# SCH_Argon_flow_controller_2021-09-10.net
KiCad netlist of a schematic drawn in EasyEDA
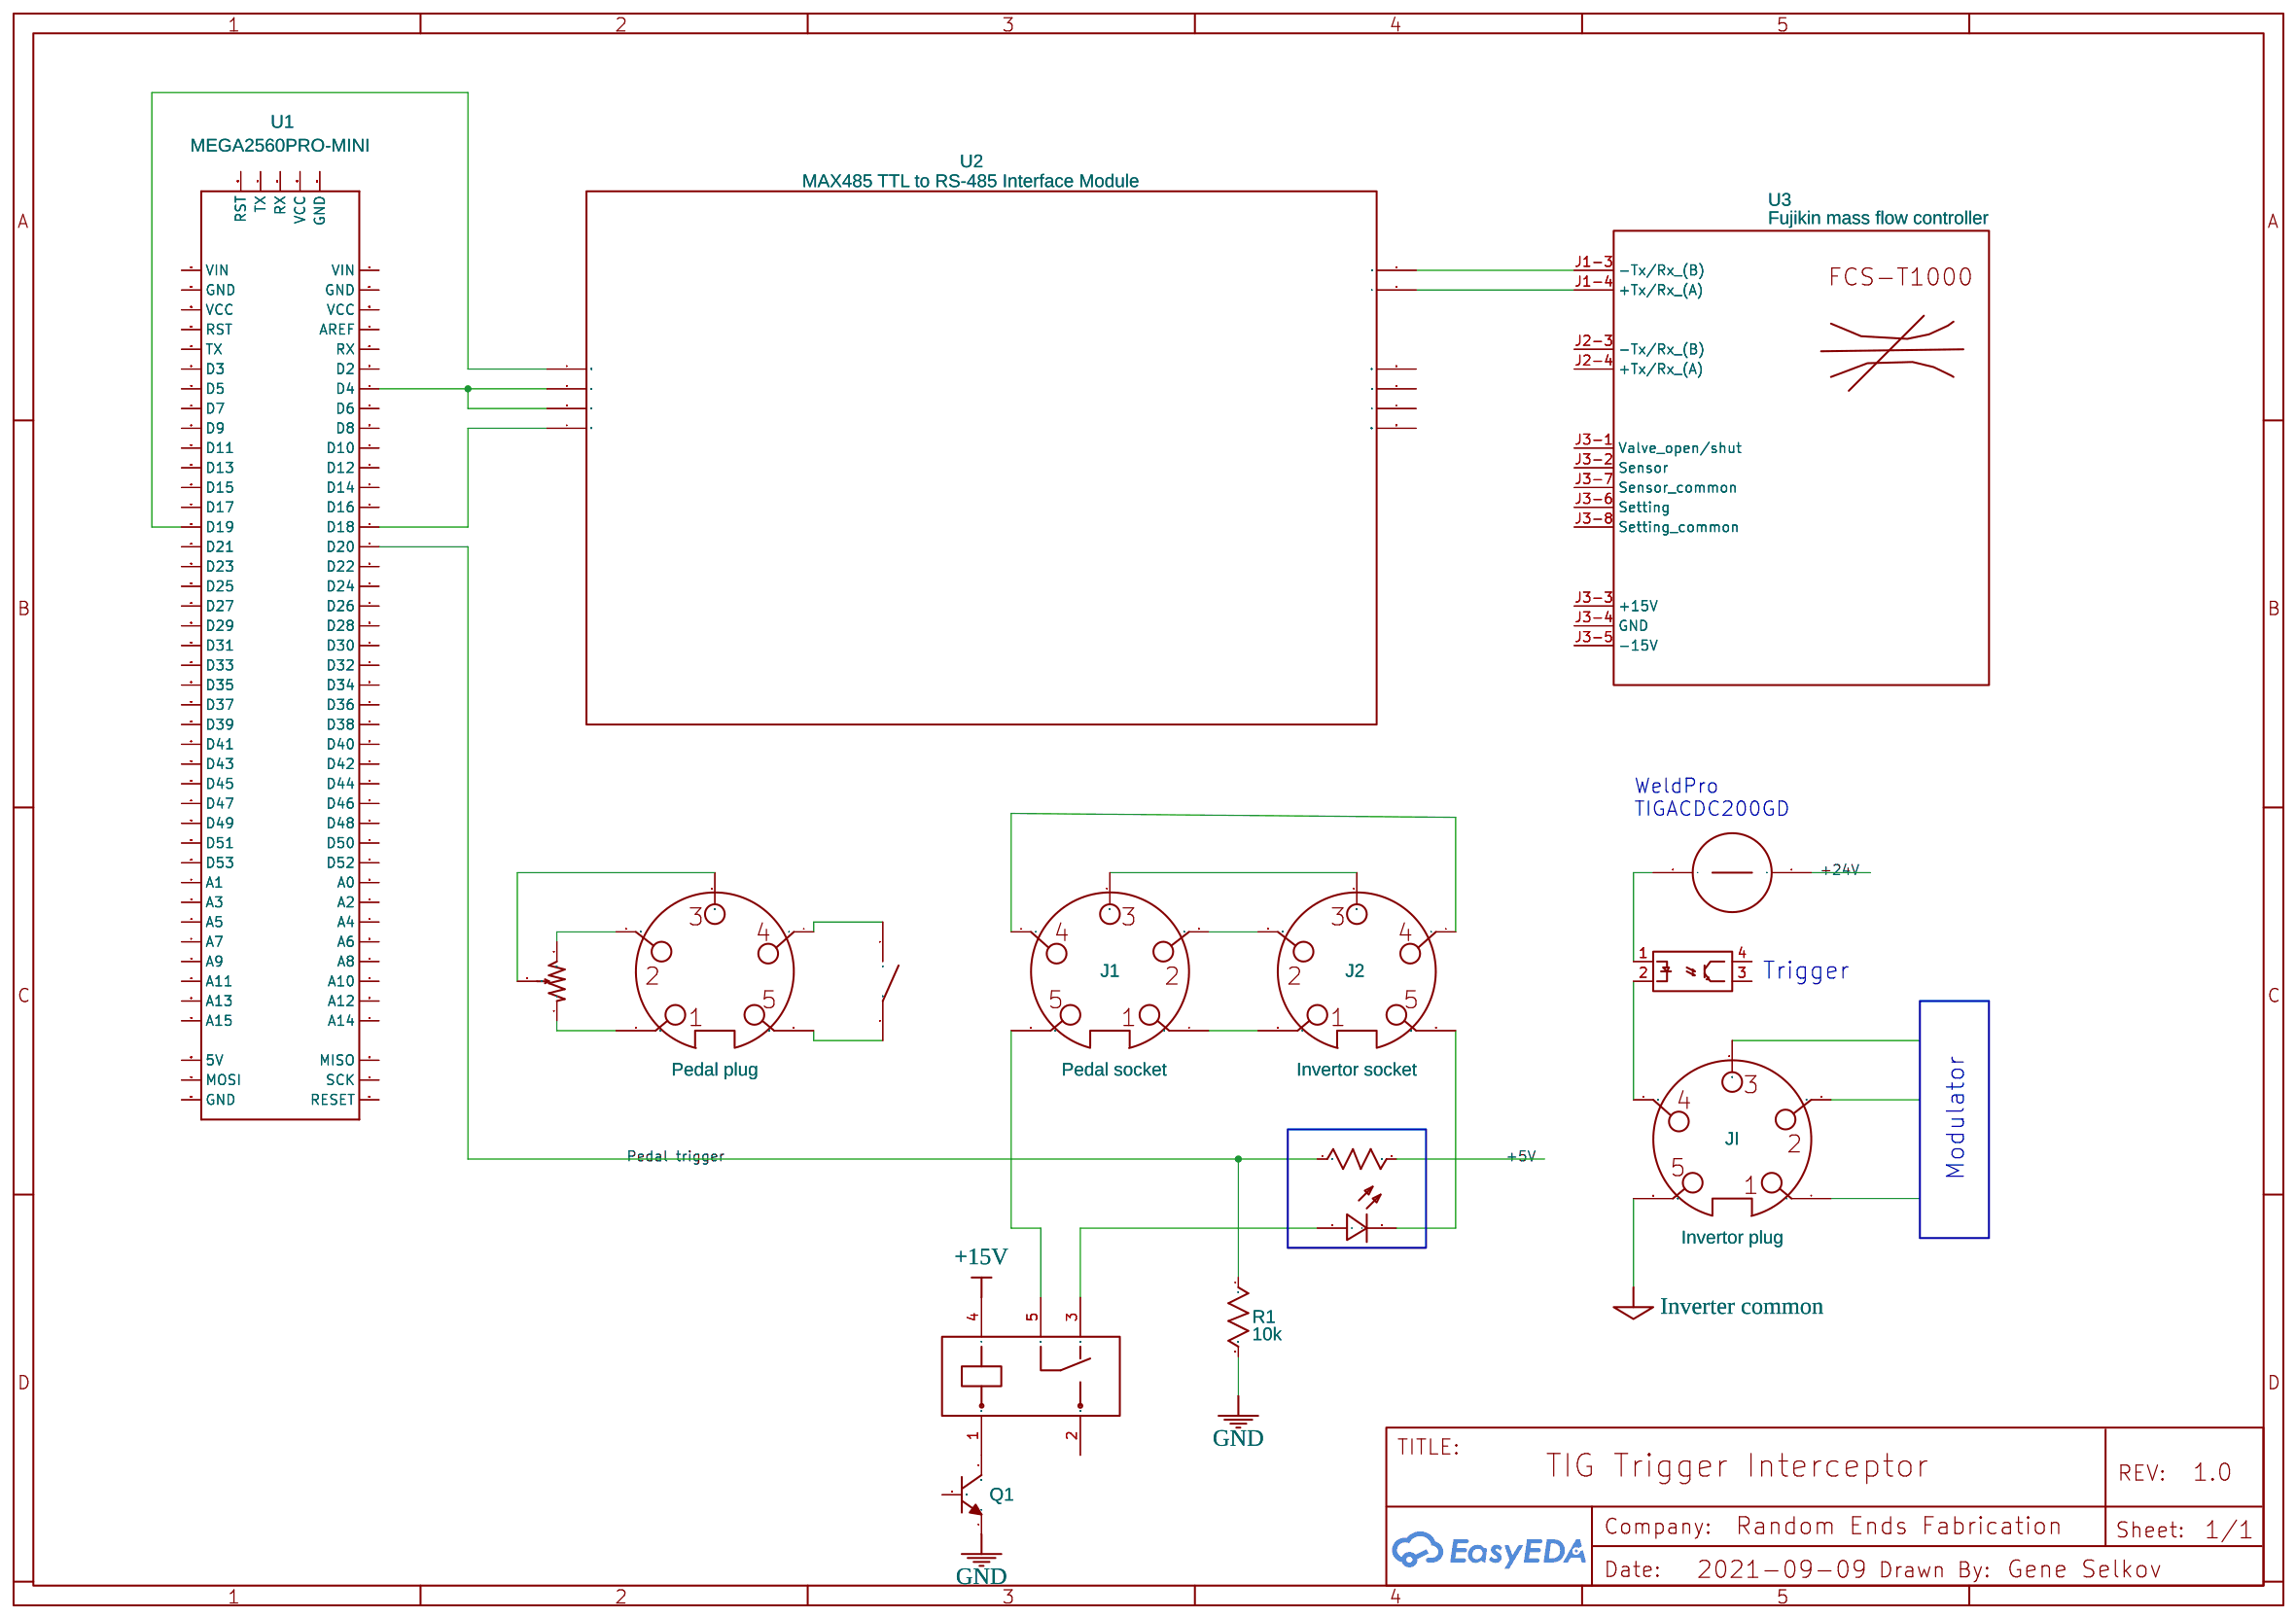
[diagram p0: schematic sheet]

(export (version "E")
  (design (tool "Eeschema 10.0.6"))
  (components
    (comp (ref "CS") (value "Current source") (libsource (lib "") (part "Current source")))
    (comp (ref "IC1")
      (value "Trigger")
      (libsource (lib "") (part "Optocoupler_SMD_KPC357_LTV35x_PC357_SingleChannel"))
    )
    (comp (ref "J0")
      (value "Pedal plug")
      (fields
        (field (name "BOM_Manufacturer Part") "Unknown")
        (field (name "BOM_Supplier Part") "CON-HK1705")
      )
      (libsource (lib "") (part "Weipu 5 connector"))
    )
    (comp (ref "J1")
      (value "Pedal socket")
      (fields
        (field (name "BOM_Manufacturer Part") "Unknown")
        (field (name "BOM_Supplier Part") "CON-HK1705")
      )
      (libsource (lib "") (part "Weipu 5 connector_3"))
    )
    (comp (ref "J2")
      (value "Invertor socket")
      (fields
        (field (name "BOM_Manufacturer Part") "Unknown")
        (field (name "BOM_Supplier Part") "CON-HK1705")
      )
      (libsource (lib "") (part "Weipu 5 connector_2"))
    )
    (comp (ref "JI")
      (value "Invertor plug")
      (fields
        (field (name "BOM_Manufacturer Part") "Unknown")
        (field (name "BOM_Supplier Part") "CON-HK1705")
      )
      (libsource (lib "") (part "Weipu 5 connector_1"))
    )
    (comp (ref "LED1")
      (value "LED-Red(0805)")
      (fields
        (field (name "BOM_Manufacturer Part") "17-21SURC/S530-A2/TR8")
        (field (name "BOM_Supplier Part") "C131244")
      )
      (libsource (lib "") (part "LED-Red(0805)"))
    )
    (comp (ref "PHR") (value "1 .. 40k") (libsource (lib "") (part "R_0603_US_1")))
    (comp (ref "POT") (value "POTENTIOMETER") (libsource (lib "") (part "POTENTIOMETER")))
    (comp (ref "Q1")
      (value "MPSA06-AT/P")
      (fields (field (name "BOM_Supplier Part") "C112894"))
      (libsource (lib "") (part "MPSA06-AT/P"))
    )
    (comp (ref "R1") (value "10k") (libsource (lib "") (part "R_0603_US")))
    (comp (ref "RELAY1")
      (value "SRD-12VDC-SL-C")
      (fields (field (name "BOM_Supplier Part") "C30431"))
      (libsource (lib "") (part "SRD-12VDC-SL-C"))
    )
    (comp (ref "S1") (value "Switch") (libsource (lib "") (part "Switch")))
    (comp (ref "U1") (value "MEGA2560PRO-MINI") (libsource (lib "") (part "MEGA2560PRO-MINI")))
    (comp (ref "U2")
      (value "MAX485 TTL to RS-485 Interface Module")
      (libsource (lib "") (part "MAX485 TTL to RS-485 Interface Module"))
    )
    (comp (ref "U3")
      (value "Fujikin mass flow controller")
      (fields (field (name "BOM_Manufacturer Part") "FCS-T1000"))
      (libsource (lib "") (part "Fujikin mass flow controller"))
    )
  )
  (nets
    (net (code "1") (name "+15V") (class "Default")
      (node (ref "RELAY1") (pin "4") (pinfunction "4_4") (pintype "input"))
    )
    (net (code "2") (name "/+5V") (class "Default")
      (node (ref "PHR") (pin "2") (pinfunction "2_2") (pintype "unspecified"))
    )
    (net (code "3") (name "/+24V") (class "Default")
      (node (ref "CS") (pin "1") (pinfunction "+_1") (pintype "unspecified"))
    )
    (net (code "4") (name "/Pedal trigger") (class "Default")
      (node (ref "PHR") (pin "1") (pinfunction "1_1") (pintype "unspecified"))
      (node (ref "R1") (pin "1") (pinfunction "1_1") (pintype "unspecified"))
      (node (ref "U1") (pin "D20") (pinfunction "D20_D20") (pintype "bidirectional"))
    )
    (net (code "5") (name "GND") (class "Default")
      (node (ref "Q1") (pin "1") (pinfunction "E_1") (pintype "input"))
      (node (ref "R1") (pin "2") (pinfunction "2_2") (pintype "unspecified"))
    )
    (net (code "6") (name "Inverter common") (class "Default")
      (node (ref "JI") (pin "5") (pinfunction "5_5") (pintype "unspecified"))
    )
    (net (code "7") (name "Net-(CS--)") (class "Default")
      (node (ref "CS") (pin "2") (pinfunction "-_2") (pintype "unspecified"))
      (node (ref "IC1") (pin "1") (pintype "unspecified"))
    )
    (net (code "8") (name "Net-(IC1-Pad2)") (class "Default")
      (node (ref "IC1") (pin "2") (pintype "unspecified"))
      (node (ref "JI") (pin "4") (pinfunction "4_4") (pintype "unspecified"))
    )
    (net (code "9") (name "Net-(J0-Pad1)") (class "Default")
      (node (ref "J0") (pin "1") (pinfunction "1_1") (pintype "unspecified"))
      (node (ref "POT") (pin "1") (pinfunction "1_1") (pintype "unspecified"))
    )
    (net (code "10") (name "Net-(J0-Pad2)") (class "Default")
      (node (ref "J0") (pin "2") (pinfunction "2_2") (pintype "unspecified"))
      (node (ref "POT") (pin "2") (pinfunction "2_2") (pintype "unspecified"))
    )
    (net (code "11") (name "Net-(J0-Pad3)") (class "Default")
      (node (ref "J0") (pin "3") (pinfunction "3_3") (pintype "unspecified"))
      (node (ref "POT") (pin "3") (pinfunction "3_3") (pintype "unspecified"))
    )
    (net (code "12") (name "Net-(J0-Pad4)") (class "Default")
      (node (ref "J0") (pin "4") (pinfunction "4_4") (pintype "unspecified"))
      (node (ref "S1") (pin "1") (pinfunction "1_1") (pintype "unspecified"))
    )
    (net (code "13") (name "Net-(J0-Pad5)") (class "Default")
      (node (ref "J0") (pin "5") (pinfunction "5_5") (pintype "unspecified"))
      (node (ref "S1") (pin "2") (pinfunction "2_2") (pintype "unspecified"))
    )
    (net (code "14") (name "Net-(J1-Pad1)") (class "Default")
      (node (ref "J1") (pin "1") (pinfunction "1_1") (pintype "unspecified"))
      (node (ref "J2") (pin "1") (pinfunction "1_1") (pintype "unspecified"))
    )
    (net (code "15") (name "Net-(J1-Pad2)") (class "Default")
      (node (ref "J1") (pin "2") (pinfunction "2_2") (pintype "unspecified"))
      (node (ref "J2") (pin "2") (pinfunction "2_2") (pintype "unspecified"))
    )
    (net (code "16") (name "Net-(J1-Pad3)") (class "Default")
      (node (ref "J1") (pin "3") (pinfunction "3_3") (pintype "unspecified"))
      (node (ref "J2") (pin "3") (pinfunction "3_3") (pintype "unspecified"))
    )
    (net (code "17") (name "Net-(J1-Pad4)") (class "Default")
      (node (ref "J1") (pin "4") (pinfunction "4_4") (pintype "unspecified"))
      (node (ref "J2") (pin "4") (pinfunction "4_4") (pintype "unspecified"))
    )
    (net (code "18") (name "Net-(J1-Pad5)") (class "Default")
      (node (ref "J1") (pin "5") (pinfunction "5_5") (pintype "unspecified"))
      (node (ref "RELAY1") (pin "5") (pinfunction "5_5") (pintype "input"))
    )
    (net (code "19") (name "Net-(LED1-+)") (class "Default")
      (node (ref "LED1") (pin "1") (pinfunction "+_1") (pintype "unspecified"))
      (node (ref "RELAY1") (pin "3") (pinfunction "3_3") (pintype "input"))
    )
    (net (code "20") (name "Net-(LED1--)") (class "Default")
      (node (ref "J2") (pin "5") (pinfunction "5_5") (pintype "unspecified"))
      (node (ref "LED1") (pin "2") (pinfunction "-_2") (pintype "unspecified"))
    )
    (net (code "21") (name "Net-(Q1-C)") (class "Default")
      (node (ref "Q1") (pin "3") (pinfunction "C_3") (pintype "input"))
      (node (ref "RELAY1") (pin "1") (pinfunction "1_1") (pintype "input"))
    )
    (net (code "22") (name "Net-(U2-A-Pad10)") (class "Default")
      (node (ref "U2") (pin "10") (pinfunction "A_10") (pintype "bidirectional"))
      (node (ref "U3") (pin "J1-4") (pinfunction "+Tx/Rx_(A)_J1-4") (pintype "bidirectional"))
    )
    (net (code "23") (name "Net-(U2-B-Pad9)") (class "Default")
      (node (ref "U2") (pin "9") (pinfunction "B_9") (pintype "bidirectional"))
      (node (ref "U3") (pin "J1-3") (pinfunction "-Tx/Rx_(B)_J1-3") (pintype "bidirectional"))
    )
    (net (code "24") (name "Net-(U2-DE)") (class "Default")
      (node (ref "U1") (pin "D4") (pinfunction "D4_D4") (pintype "bidirectional"))
      (node (ref "U2") (pin "2") (pinfunction "RE_2") (pintype "input"))
      (node (ref "U2") (pin "3") (pinfunction "DE_3") (pintype "input"))
    )
    (net (code "25") (name "Net-(U2-DI)") (class "Default")
      (node (ref "U1") (pin "D18") (pinfunction "D18_D18") (pintype "bidirectional"))
      (node (ref "U2") (pin "4") (pinfunction "DI_4") (pintype "input"))
    )
    (net (code "26") (name "Net-(U2-RO)") (class "Default")
      (node (ref "U1") (pin "D19") (pinfunction "D19_D19") (pintype "bidirectional"))
      (node (ref "U2") (pin "1") (pinfunction "RO_1") (pintype "output"))
    )
    (net (code "27") (name "unconnected-(IC1-Pad3)") (class "Default")
      (node (ref "IC1") (pin "3") (pintype "unspecified"))
    )
    (net (code "28") (name "unconnected-(IC1-Pad4)") (class "Default")
      (node (ref "IC1") (pin "4") (pintype "unspecified"))
    )
    (net (code "29") (name "unconnected-(JI-Pad1)") (class "Default")
      (node (ref "JI") (pin "1") (pinfunction "1_1") (pintype "unspecified"))
    )
    (net (code "30") (name "unconnected-(JI-Pad2)") (class "Default")
      (node (ref "JI") (pin "2") (pinfunction "2_2") (pintype "unspecified"))
    )
    (net (code "31") (name "unconnected-(JI-Pad3)") (class "Default")
      (node (ref "JI") (pin "3") (pinfunction "3_3") (pintype "unspecified"))
    )
    (net (code "32") (name "unconnected-(Q1-B-Pad2)") (class "Default")
      (node (ref "Q1") (pin "2") (pinfunction "B_2") (pintype "input"))
    )
    (net (code "33") (name "unconnected-(RELAY1-Pad2)") (class "Default")
      (node (ref "RELAY1") (pin "2") (pinfunction "2_2") (pintype "input"))
    )
    (net (code "34") (name "unconnected-(U1-5V-Pad5V@3)") (class "Default")
      (node (ref "U1") (pin "5V@3") (pinfunction "5V_5V@3") (pintype "bidirectional"))
    )
    (net (code "35") (name "unconnected-(U1-GND-PadGND@1)") (class "Default")
      (node (ref "U1") (pin "GND@1") (pinfunction "GND_GND@1") (pintype "bidirectional"))
    )
    (net (code "36") (name "unconnected-(U1-GND-PadGND@2)") (class "Default")
      (node (ref "U1") (pin "GND@2") (pinfunction "GND_GND@2") (pintype "bidirectional"))
    )
    (net (code "37") (name "unconnected-(U1-GND-PadGND@3)") (class "Default")
      (node (ref "U1") (pin "GND@3") (pinfunction "GND_GND@3") (pintype "bidirectional"))
    )
    (net (code "38") (name "unconnected-(U1-GND-PadGND@4)") (class "Default")
      (node (ref "U1") (pin "GND@4") (pinfunction "GND_GND@4") (pintype "bidirectional"))
    )
    (net (code "39") (name "unconnected-(U1-PadA0)") (class "Default")
      (node (ref "U1") (pin "A0") (pinfunction "A0_A0") (pintype "bidirectional"))
    )
    (net (code "40") (name "unconnected-(U1-PadA1)") (class "Default")
      (node (ref "U1") (pin "A1") (pinfunction "A1_A1") (pintype "bidirectional"))
    )
    (net (code "41") (name "unconnected-(U1-PadA2)") (class "Default")
      (node (ref "U1") (pin "A2") (pinfunction "A2_A2") (pintype "bidirectional"))
    )
    (net (code "42") (name "unconnected-(U1-PadA3)") (class "Default")
      (node (ref "U1") (pin "A3") (pinfunction "A3_A3") (pintype "bidirectional"))
    )
    (net (code "43") (name "unconnected-(U1-PadA4)") (class "Default")
      (node (ref "U1") (pin "A4") (pinfunction "A4_A4") (pintype "bidirectional"))
    )
    (net (code "44") (name "unconnected-(U1-PadA5)") (class "Default")
      (node (ref "U1") (pin "A5") (pinfunction "A5_A5") (pintype "bidirectional"))
    )
    (net (code "45") (name "unconnected-(U1-PadA6)") (class "Default")
      (node (ref "U1") (pin "A6") (pinfunction "A6_A6") (pintype "bidirectional"))
    )
    (net (code "46") (name "unconnected-(U1-PadA7)") (class "Default")
      (node (ref "U1") (pin "A7") (pinfunction "A7_A7") (pintype "bidirectional"))
    )
    (net (code "47") (name "unconnected-(U1-PadA8)") (class "Default")
      (node (ref "U1") (pin "A8") (pinfunction "A8_A8") (pintype "bidirectional"))
    )
    (net (code "48") (name "unconnected-(U1-PadA9)") (class "Default")
      (node (ref "U1") (pin "A9") (pinfunction "A9_A9") (pintype "bidirectional"))
    )
    (net (code "49") (name "unconnected-(U1-PadA10)") (class "Default")
      (node (ref "U1") (pin "A10") (pinfunction "A10_A10") (pintype "bidirectional"))
    )
    (net (code "50") (name "unconnected-(U1-PadA11)") (class "Default")
      (node (ref "U1") (pin "A11") (pinfunction "A11_A11") (pintype "bidirectional"))
    )
    (net (code "51") (name "unconnected-(U1-PadA12)") (class "Default")
      (node (ref "U1") (pin "A12") (pinfunction "A12_A12") (pintype "bidirectional"))
    )
    (net (code "52") (name "unconnected-(U1-PadA13)") (class "Default")
      (node (ref "U1") (pin "A13") (pinfunction "A13_A13") (pintype "bidirectional"))
    )
    (net (code "53") (name "unconnected-(U1-PadA14)") (class "Default")
      (node (ref "U1") (pin "A14") (pinfunction "A14_A14") (pintype "bidirectional"))
    )
    (net (code "54") (name "unconnected-(U1-PadA15)") (class "Default")
      (node (ref "U1") (pin "A15") (pinfunction "A15_A15") (pintype "bidirectional"))
    )
    (net (code "55") (name "unconnected-(U1-PadAREF)") (class "Default")
      (node (ref "U1") (pin "AREF") (pinfunction "AREF_AREF") (pintype "bidirectional"))
    )
    (net (code "56") (name "unconnected-(U1-PadD2)") (class "Default")
      (node (ref "U1") (pin "D2") (pinfunction "D2_D2") (pintype "bidirectional"))
    )
    (net (code "57") (name "unconnected-(U1-PadD3)") (class "Default")
      (node (ref "U1") (pin "D3") (pinfunction "D3_D3") (pintype "bidirectional"))
    )
    (net (code "58") (name "unconnected-(U1-PadD5)") (class "Default")
      (node (ref "U1") (pin "D5") (pinfunction "D5_D5") (pintype "bidirectional"))
    )
    (net (code "59") (name "unconnected-(U1-PadD6)") (class "Default")
      (node (ref "U1") (pin "D6") (pinfunction "D6_D6") (pintype "bidirectional"))
    )
    (net (code "60") (name "unconnected-(U1-PadD7)") (class "Default")
      (node (ref "U1") (pin "D7") (pinfunction "D7_D7") (pintype "bidirectional"))
    )
    (net (code "61") (name "unconnected-(U1-PadD8)") (class "Default")
      (node (ref "U1") (pin "D8") (pinfunction "D8_D8") (pintype "bidirectional"))
    )
    (net (code "62") (name "unconnected-(U1-PadD9)") (class "Default")
      (node (ref "U1") (pin "D9") (pinfunction "D9_D9") (pintype "bidirectional"))
    )
    (net (code "63") (name "unconnected-(U1-PadD10)") (class "Default")
      (node (ref "U1") (pin "D10") (pinfunction "D10_D10") (pintype "bidirectional"))
    )
    (net (code "64") (name "unconnected-(U1-PadD11)") (class "Default")
      (node (ref "U1") (pin "D11") (pinfunction "D11_D11") (pintype "bidirectional"))
    )
    (net (code "65") (name "unconnected-(U1-PadD12)") (class "Default")
      (node (ref "U1") (pin "D12") (pinfunction "D12_D12") (pintype "bidirectional"))
    )
    (net (code "66") (name "unconnected-(U1-PadD13)") (class "Default")
      (node (ref "U1") (pin "D13") (pinfunction "D13_D13") (pintype "bidirectional"))
    )
    (net (code "67") (name "unconnected-(U1-PadD14)") (class "Default")
      (node (ref "U1") (pin "D14") (pinfunction "D14_D14") (pintype "bidirectional"))
    )
    (net (code "68") (name "unconnected-(U1-PadD15)") (class "Default")
      (node (ref "U1") (pin "D15") (pinfunction "D15_D15") (pintype "bidirectional"))
    )
    (net (code "69") (name "unconnected-(U1-PadD16)") (class "Default")
      (node (ref "U1") (pin "D16") (pinfunction "D16_D16") (pintype "bidirectional"))
    )
    (net (code "70") (name "unconnected-(U1-PadD17)") (class "Default")
      (node (ref "U1") (pin "D17") (pinfunction "D17_D17") (pintype "bidirectional"))
    )
    (net (code "71") (name "unconnected-(U1-PadD21)") (class "Default")
      (node (ref "U1") (pin "D21") (pinfunction "D21_D21") (pintype "bidirectional"))
    )
    (net (code "72") (name "unconnected-(U1-PadD22)") (class "Default")
      (node (ref "U1") (pin "D22") (pinfunction "D22_D22") (pintype "bidirectional"))
    )
    (net (code "73") (name "unconnected-(U1-PadD23)") (class "Default")
      (node (ref "U1") (pin "D23") (pinfunction "D23_D23") (pintype "bidirectional"))
    )
    (net (code "74") (name "unconnected-(U1-PadD24)") (class "Default")
      (node (ref "U1") (pin "D24") (pinfunction "D24_D24") (pintype "bidirectional"))
    )
    (net (code "75") (name "unconnected-(U1-PadD25)") (class "Default")
      (node (ref "U1") (pin "D25") (pinfunction "D25_D25") (pintype "bidirectional"))
    )
    (net (code "76") (name "unconnected-(U1-PadD26)") (class "Default")
      (node (ref "U1") (pin "D26") (pinfunction "D26_D26") (pintype "bidirectional"))
    )
    (net (code "77") (name "unconnected-(U1-PadD27)") (class "Default")
      (node (ref "U1") (pin "D27") (pinfunction "D27_D27") (pintype "bidirectional"))
    )
    (net (code "78") (name "unconnected-(U1-PadD28)") (class "Default")
      (node (ref "U1") (pin "D28") (pinfunction "D28_D28") (pintype "bidirectional"))
    )
    (net (code "79") (name "unconnected-(U1-PadD29)") (class "Default")
      (node (ref "U1") (pin "D29") (pinfunction "D29_D29") (pintype "bidirectional"))
    )
    (net (code "80") (name "unconnected-(U1-PadD30)") (class "Default")
      (node (ref "U1") (pin "D30") (pinfunction "D30_D30") (pintype "bidirectional"))
    )
    (net (code "81") (name "unconnected-(U1-PadD31)") (class "Default")
      (node (ref "U1") (pin "D31") (pinfunction "D31_D31") (pintype "bidirectional"))
    )
    (net (code "82") (name "unconnected-(U1-PadD32)") (class "Default")
      (node (ref "U1") (pin "D32") (pinfunction "D32_D32") (pintype "bidirectional"))
    )
    (net (code "83") (name "unconnected-(U1-PadD33)") (class "Default")
      (node (ref "U1") (pin "D33") (pinfunction "D33_D33") (pintype "bidirectional"))
    )
    (net (code "84") (name "unconnected-(U1-PadD34)") (class "Default")
      (node (ref "U1") (pin "D34") (pinfunction "D34_D34") (pintype "bidirectional"))
    )
    (net (code "85") (name "unconnected-(U1-PadD35)") (class "Default")
      (node (ref "U1") (pin "D35") (pinfunction "D35_D35") (pintype "bidirectional"))
    )
    (net (code "86") (name "unconnected-(U1-PadD36)") (class "Default")
      (node (ref "U1") (pin "D36") (pinfunction "D36_D36") (pintype "bidirectional"))
    )
    (net (code "87") (name "unconnected-(U1-PadD37)") (class "Default")
      (node (ref "U1") (pin "D37") (pinfunction "D37_D37") (pintype "bidirectional"))
    )
    (net (code "88") (name "unconnected-(U1-PadD38)") (class "Default")
      (node (ref "U1") (pin "D38") (pinfunction "D38_D38") (pintype "bidirectional"))
    )
    (net (code "89") (name "unconnected-(U1-PadD39)") (class "Default")
      (node (ref "U1") (pin "D39") (pinfunction "D39_D39") (pintype "bidirectional"))
    )
    (net (code "90") (name "unconnected-(U1-PadD40)") (class "Default")
      (node (ref "U1") (pin "D40") (pinfunction "D40_D40") (pintype "bidirectional"))
    )
    (net (code "91") (name "unconnected-(U1-PadD41)") (class "Default")
      (node (ref "U1") (pin "D41") (pinfunction "D41_D41") (pintype "bidirectional"))
    )
    (net (code "92") (name "unconnected-(U1-PadD42)") (class "Default")
      (node (ref "U1") (pin "D42") (pinfunction "D42_D42") (pintype "bidirectional"))
    )
    (net (code "93") (name "unconnected-(U1-PadD43)") (class "Default")
      (node (ref "U1") (pin "D43") (pinfunction "D43_D43") (pintype "bidirectional"))
    )
    (net (code "94") (name "unconnected-(U1-PadD44)") (class "Default")
      (node (ref "U1") (pin "D44") (pinfunction "D44_D44") (pintype "bidirectional"))
    )
    (net (code "95") (name "unconnected-(U1-PadD45)") (class "Default")
      (node (ref "U1") (pin "D45") (pinfunction "D45_D45") (pintype "bidirectional"))
    )
    (net (code "96") (name "unconnected-(U1-PadD46)") (class "Default")
      (node (ref "U1") (pin "D46") (pinfunction "D46_D46") (pintype "bidirectional"))
    )
    (net (code "97") (name "unconnected-(U1-PadD47)") (class "Default")
      (node (ref "U1") (pin "D47") (pinfunction "D47_D47") (pintype "bidirectional"))
    )
    (net (code "98") (name "unconnected-(U1-PadD48)") (class "Default")
      (node (ref "U1") (pin "D48") (pinfunction "D48_D48") (pintype "bidirectional"))
    )
    (net (code "99") (name "unconnected-(U1-PadD49)") (class "Default")
      (node (ref "U1") (pin "D49") (pinfunction "D49_D49") (pintype "bidirectional"))
    )
    (net (code "100") (name "unconnected-(U1-PadD50)") (class "Default")
      (node (ref "U1") (pin "D50") (pinfunction "D50_D50") (pintype "bidirectional"))
    )
    (net (code "101") (name "unconnected-(U1-PadD51)") (class "Default")
      (node (ref "U1") (pin "D51") (pinfunction "D51_D51") (pintype "bidirectional"))
    )
    (net (code "102") (name "unconnected-(U1-PadD52)") (class "Default")
      (node (ref "U1") (pin "D52") (pinfunction "D52_D52") (pintype "bidirectional"))
    )
    (net (code "103") (name "unconnected-(U1-PadD53)") (class "Default")
      (node (ref "U1") (pin "D53") (pinfunction "D53_D53") (pintype "bidirectional"))
    )
    (net (code "104") (name "unconnected-(U1-PadMISO)") (class "Default")
      (node (ref "U1") (pin "MISO") (pinfunction "MISO_MISO") (pintype "bidirectional"))
    )
    (net (code "105") (name "unconnected-(U1-PadMOSI)") (class "Default")
      (node (ref "U1") (pin "MOSI") (pinfunction "MOSI_MOSI") (pintype "bidirectional"))
    )
    (net (code "106") (name "unconnected-(U1-PadRESET)") (class "Default")
      (node (ref "U1") (pin "RESET") (pinfunction "RESET_RESET") (pintype "bidirectional"))
    )
    (net (code "107") (name "unconnected-(U1-PadSCK)") (class "Default")
      (node (ref "U1") (pin "SCK") (pinfunction "SCK_SCK") (pintype "bidirectional"))
    )
    (net (code "108") (name "unconnected-(U1-RST-PadRST@1)") (class "Default")
      (node (ref "U1") (pin "RST@1") (pinfunction "RST_RST@1") (pintype "bidirectional"))
    )
    (net (code "109") (name "unconnected-(U1-RST-PadRST@2)") (class "Default")
      (node (ref "U1") (pin "RST@2") (pinfunction "RST_RST@2") (pintype "bidirectional"))
    )
    (net (code "110") (name "unconnected-(U1-RX-PadRX@1)") (class "Default")
      (node (ref "U1") (pin "RX@1") (pinfunction "RX_RX@1") (pintype "bidirectional"))
    )
    (net (code "111") (name "unconnected-(U1-RX-PadRX@2)") (class "Default")
      (node (ref "U1") (pin "RX@2") (pinfunction "RX_RX@2") (pintype "bidirectional"))
    )
    (net (code "112") (name "unconnected-(U1-TX-PadTX@1)") (class "Default")
      (node (ref "U1") (pin "TX@1") (pinfunction "TX_TX@1") (pintype "bidirectional"))
    )
    (net (code "113") (name "unconnected-(U1-TX-PadTX@2)") (class "Default")
      (node (ref "U1") (pin "TX@2") (pinfunction "TX_TX@2") (pintype "bidirectional"))
    )
    (net (code "114") (name "unconnected-(U1-VCC-PadVCC@1)") (class "Default")
      (node (ref "U1") (pin "VCC@1") (pinfunction "VCC_VCC@1") (pintype "bidirectional"))
    )
    (net (code "115") (name "unconnected-(U1-VCC-PadVCC@2)") (class "Default")
      (node (ref "U1") (pin "VCC@2") (pinfunction "VCC_VCC@2") (pintype "bidirectional"))
    )
    (net (code "116") (name "unconnected-(U1-VCC-PadVCC@3)") (class "Default")
      (node (ref "U1") (pin "VCC@3") (pinfunction "VCC_VCC@3") (pintype "bidirectional"))
    )
    (net (code "117") (name "unconnected-(U1-VIN-PadVIN@1)") (class "Default")
      (node (ref "U1") (pin "VIN@1") (pinfunction "VIN_VIN@1") (pintype "bidirectional"))
    )
    (net (code "118") (name "unconnected-(U1-VIN-PadVIN@2)") (class "Default")
      (node (ref "U1") (pin "VIN@2") (pinfunction "VIN_VIN@2") (pintype "bidirectional"))
    )
    (net (code "119") (name "unconnected-(U2-5V-Pad5)") (class "Default")
      (node (ref "U2") (pin "5") (pinfunction "5V_5") (pintype "passive"))
    )
    (net (code "120") (name "unconnected-(U2-A-Pad7)") (class "Default")
      (node (ref "U2") (pin "7") (pinfunction "A_7") (pintype "bidirectional"))
    )
    (net (code "121") (name "unconnected-(U2-B-Pad6)") (class "Default")
      (node (ref "U2") (pin "6") (pinfunction "B_6") (pintype "bidirectional"))
    )
    (net (code "122") (name "unconnected-(U2-GND-Pad8)") (class "Default")
      (node (ref "U2") (pin "8") (pinfunction "GND_8") (pintype "passive"))
    )
    (net (code "123") (name "unconnected-(U3-+15V-PadJ3-3)") (class "Default")
      (node (ref "U3") (pin "J3-3") (pinfunction "+15V_J3-3") (pintype "passive"))
    )
    (net (code "124") (name "unconnected-(U3-+Tx{slash}Rx_(A)-PadJ2-4)") (class "Default")
      (node (ref "U3") (pin "J2-4") (pinfunction "+Tx/Rx_(A)_J2-4") (pintype "bidirectional"))
    )
    (net (code "125") (name "unconnected-(U3--15V-PadJ3-5)") (class "Default")
      (node (ref "U3") (pin "J3-5") (pinfunction "-15V_J3-5") (pintype "passive"))
    )
    (net (code "126") (name "unconnected-(U3--Tx{slash}Rx_(B)-PadJ2-3)") (class "Default")
      (node (ref "U3") (pin "J2-3") (pinfunction "-Tx/Rx_(B)_J2-3") (pintype "bidirectional"))
    )
    (net (code "127") (name "unconnected-(U3-GND-PadJ3-4)") (class "Default")
      (node (ref "U3") (pin "J3-4") (pinfunction "GND_J3-4") (pintype "passive"))
    )
    (net (code "128") (name "unconnected-(U3-Sensor-PadJ3-2)") (class "Default")
      (node (ref "U3") (pin "J3-2") (pinfunction "Sensor_J3-2") (pintype "output"))
    )
    (net (code "129") (name "unconnected-(U3-Sensor_common-PadJ3-7)") (class "Default")
      (node (ref "U3") (pin "J3-7") (pinfunction "Sensor_common_J3-7") (pintype "output"))
    )
    (net (code "130") (name "unconnected-(U3-Setting-PadJ3-6)") (class "Default")
      (node (ref "U3") (pin "J3-6") (pinfunction "Setting_J3-6") (pintype "input"))
    )
    (net (code "131") (name "unconnected-(U3-Setting_common-PadJ3-8)") (class "Default")
      (node (ref "U3") (pin "J3-8") (pinfunction "Setting_common_J3-8") (pintype "input"))
    )
    (net (code "132") (name "unconnected-(U3-Valve_open{slash}shut-PadJ3-1)") (class "Default")
      (node (ref "U3") (pin "J3-1") (pinfunction "Valve_open/shut_J3-1") (pintype "unspecified"))
    )
  )
)
